# v6_io_12_13_14_15.net
KiCad netlist of a schematic drawn in Altium Designer
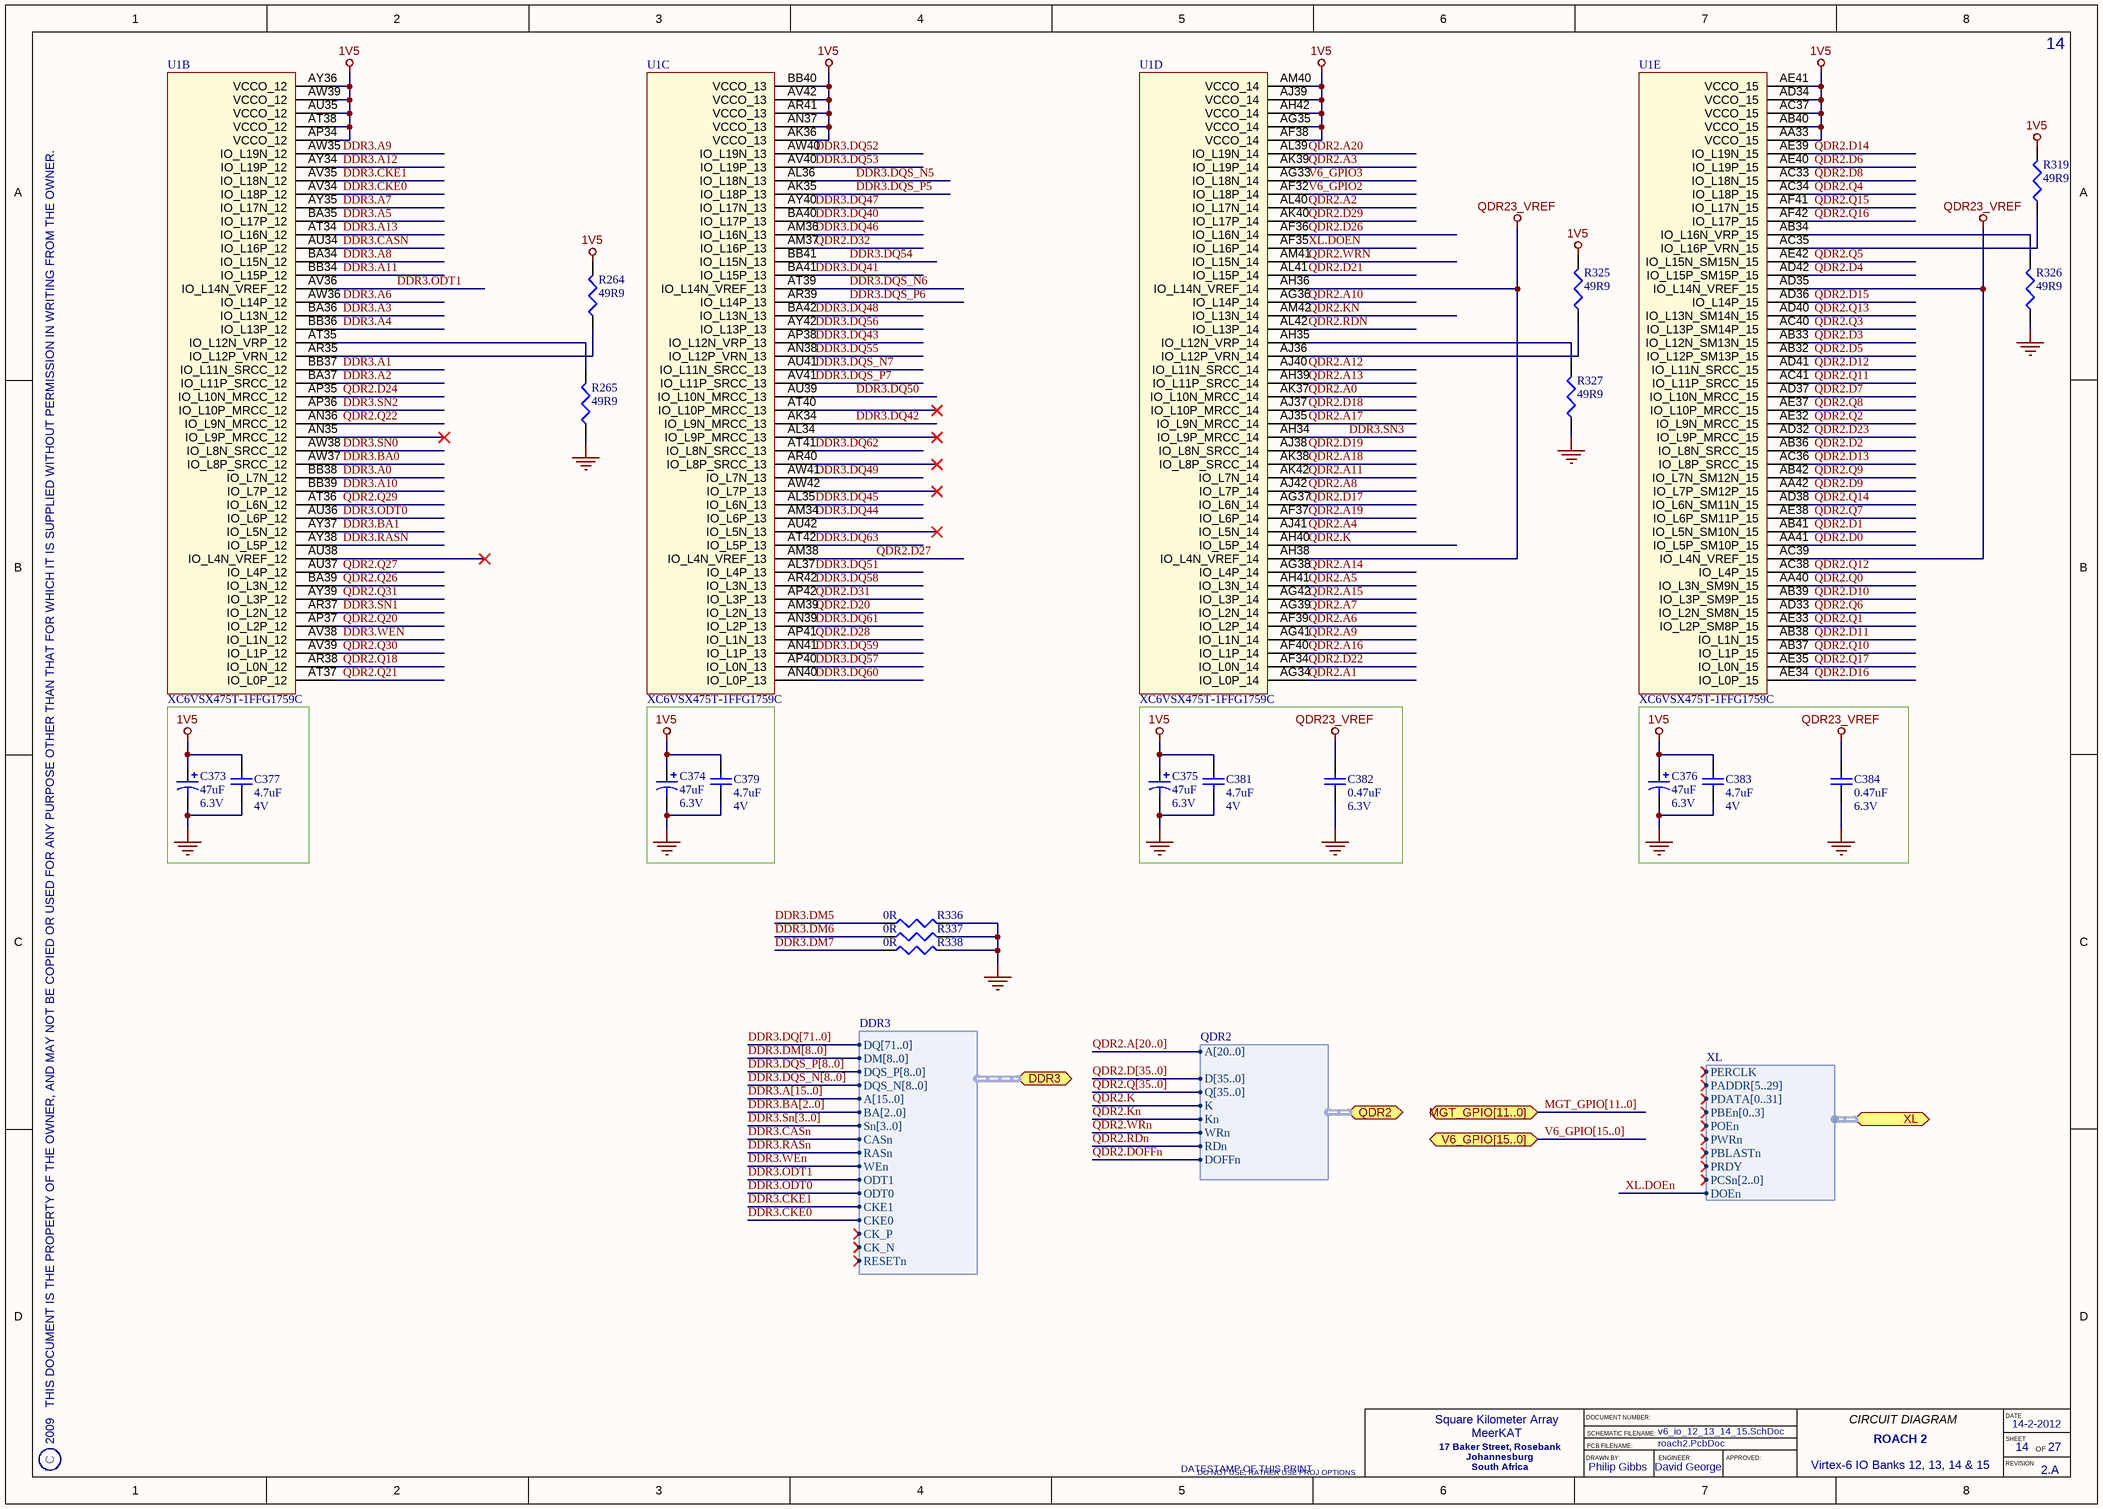
[diagram p0: v6_io_12_13_14_15.SchDoc]

(export (version "E")
  (design (tool "Eeschema 10.0.6"))
  (components
    (comp (ref "C373")
      (value "47uF")
      (footprint "CAPMP3528X120L")
      (description "47uF, Conductive Polymer Chip Capacitor")
      (fields
        (field (name "RATING") "6.3V")
        (field (name "MANUFACTURER") "KEMET")
        (field (name "PARTNUM") "T520T476M006ATE070")
      )
      (libsource (lib "altium_db") (part "CapPol"))
    )
    (comp (ref "C374")
      (value "47uF")
      (footprint "CAPMP3528X120L")
      (description "47uF, Conductive Polymer Chip Capacitor")
      (fields
        (field (name "RATING") "6.3V")
        (field (name "MANUFACTURER") "KEMET")
        (field (name "PARTNUM") "T520T476M006ATE070")
      )
      (libsource (lib "altium_db") (part "CapPol"))
    )
    (comp (ref "C375")
      (value "47uF")
      (footprint "CAPMP3528X120L")
      (description "47uF, Conductive Polymer Chip Capacitor")
      (fields
        (field (name "RATING") "6.3V")
        (field (name "MANUFACTURER") "KEMET")
        (field (name "PARTNUM") "T520T476M006ATE070")
      )
      (libsource (lib "altium_db") (part "CapPol"))
    )
    (comp (ref "C376")
      (value "47uF")
      (footprint "CAPMP3528X120L")
      (description "47uF, Conductive Polymer Chip Capacitor")
      (fields
        (field (name "RATING") "6.3V")
        (field (name "MANUFACTURER") "KEMET")
        (field (name "PARTNUM") "T520T476M006ATE070")
      )
      (libsource (lib "altium_db") (part "CapPol"))
    )
    (comp (ref "C377")
      (value "4.7uF")
      (footprint "CAPC1005X60L")
      (description "4.7uF, Ceramic Capacitor")
      (fields
        (field (name "RATING") "4V")
        (field (name "MANUFACTURER") "MURATA")
        (field (name "PARTNUM") "AMK105BJ475MV-F")
      )
      (libsource (lib "altium_db") (part "CapStd"))
    )
    (comp (ref "C379")
      (value "4.7uF")
      (footprint "CAPC1005X60L")
      (description "4.7uF, Ceramic Capacitor")
      (fields
        (field (name "RATING") "4V")
        (field (name "MANUFACTURER") "MURATA")
        (field (name "PARTNUM") "AMK105BJ475MV-F")
      )
      (libsource (lib "altium_db") (part "CapStd"))
    )
    (comp (ref "C381")
      (value "4.7uF")
      (footprint "CAPC1005X60L")
      (description "4.7uF, Ceramic Capacitor")
      (fields
        (field (name "RATING") "4V")
        (field (name "MANUFACTURER") "MURATA")
        (field (name "PARTNUM") "AMK105BJ475MV-F")
      )
      (libsource (lib "altium_db") (part "CapStd"))
    )
    (comp (ref "C382")
      (value "0.47uF")
      (footprint "CAPC1005X55L")
      (description "0.47uF, Ceramic Capacitor")
      (fields
        (field (name "RATING") "6.3V")
        (field (name "MANUFACTURER") "MURATA")
        (field (name "PARTNUM") "GRM155R60J474KE19")
      )
      (libsource (lib "altium_db") (part "CapStd"))
    )
    (comp (ref "C383")
      (value "4.7uF")
      (footprint "CAPC1005X60L")
      (description "4.7uF, Ceramic Capacitor")
      (fields
        (field (name "RATING") "4V")
        (field (name "MANUFACTURER") "MURATA")
        (field (name "PARTNUM") "AMK105BJ475MV-F")
      )
      (libsource (lib "altium_db") (part "CapStd"))
    )
    (comp (ref "C384")
      (value "0.47uF")
      (footprint "CAPC1005X55L")
      (description "0.47uF, Ceramic Capacitor")
      (fields
        (field (name "RATING") "6.3V")
        (field (name "MANUFACTURER") "MURATA")
        (field (name "PARTNUM") "GRM155R60J474KE19")
      )
      (libsource (lib "altium_db") (part "CapStd"))
    )
    (comp (ref "R264")
      (value "49R9")
      (footprint "RESC1005X40L")
      (description "49R9, 1.1mm x 0.5mm, Thick Film Resistor")
      (fields (field (name "MANUFACTURER") "ROYALOHM") (field (name "PARTNUM") "0402WGF499JT1E"))
      (libsource (lib "altium_db") (part "ResStd"))
    )
    (comp (ref "R265")
      (value "49R9")
      (footprint "RESC1005X40L")
      (description "49R9, 1.1mm x 0.5mm, Thick Film Resistor")
      (fields (field (name "MANUFACTURER") "ROYALOHM") (field (name "PARTNUM") "0402WGF499JT1E"))
      (libsource (lib "altium_db") (part "ResStd"))
    )
    (comp (ref "R319")
      (value "49R9")
      (footprint "RESC1005X40L")
      (description "49R9, 1.1mm x 0.5mm, Thick Film Resistor")
      (fields (field (name "MANUFACTURER") "ROYALOHM") (field (name "PARTNUM") "0402WGF499JT1E"))
      (libsource (lib "altium_db") (part "ResStd"))
    )
    (comp (ref "R325")
      (value "49R9")
      (footprint "RESC1005X40L")
      (description "49R9, 1.1mm x 0.5mm, Thick Film Resistor")
      (fields (field (name "MANUFACTURER") "ROYALOHM") (field (name "PARTNUM") "0402WGF499JT1E"))
      (libsource (lib "altium_db") (part "ResStd"))
    )
    (comp (ref "R326")
      (value "49R9")
      (footprint "RESC1005X40L")
      (description "49R9, 1.1mm x 0.5mm, Thick Film Resistor")
      (fields (field (name "MANUFACTURER") "ROYALOHM") (field (name "PARTNUM") "0402WGF499JT1E"))
      (libsource (lib "altium_db") (part "ResStd"))
    )
    (comp (ref "R327")
      (value "49R9")
      (footprint "RESC1005X40L")
      (description "49R9, 1.1mm x 0.5mm, Thick Film Resistor")
      (fields (field (name "MANUFACTURER") "ROYALOHM") (field (name "PARTNUM") "0402WGF499JT1E"))
      (libsource (lib "altium_db") (part "ResStd"))
    )
    (comp (ref "R336")
      (value "0R")
      (footprint "RESC1005X40L")
      (description "0R, 1.1mm x 0.5mm, Thick Film Resistor")
      (fields (field (name "MANUFACTURER") "ROYALOHM") (field (name "PARTNUM") "0402WG00000T1E"))
      (libsource (lib "altium_db") (part "ResStd"))
    )
    (comp (ref "R337")
      (value "0R")
      (footprint "RESC1005X40L")
      (description "0R, 1.1mm x 0.5mm, Thick Film Resistor")
      (fields (field (name "MANUFACTURER") "ROYALOHM") (field (name "PARTNUM") "0402WG00000T1E"))
      (libsource (lib "altium_db") (part "ResStd"))
    )
    (comp (ref "R338")
      (value "0R")
      (footprint "RESC1005X40L")
      (description "0R, 1.1mm x 0.5mm, Thick Film Resistor")
      (fields (field (name "MANUFACTURER") "ROYALOHM") (field (name "PARTNUM") "0402WG00000T1E"))
      (libsource (lib "altium_db") (part "ResStd"))
    )
    (comp (ref "U1")
      (value "XC6VSX475T-1FFG1759C")
      (footprint "FFG1759")
      (description "Virtex-6 475SXT 1760-pin FPGA")
      (fields (field (name "MANUFACTURER") "Xilinx"))
      (libsource (lib "altium_db") (part "XC6VSX475T-1FFG1759C"))
    )
  )
  (nets
    (net (code "113") (name "/DDR3.A0") (class "Default")
      (node (ref "U1") (pin "BB38") (pinfunction "IO_L7N_12_BB38") (pintype "passive"))
    )
    (net (code "114") (name "/DDR3.A1") (class "Default")
      (node (ref "U1") (pin "BB37") (pinfunction "IO_L11N_SRCC_12_BB37") (pintype "passive"))
    )
    (net (code "115") (name "/DDR3.A2") (class "Default")
      (node (ref "U1") (pin "BA37") (pinfunction "IO_L11P_SRCC_12_BA37") (pintype "passive"))
    )
    (net (code "116") (name "/DDR3.A3") (class "Default")
      (node (ref "U1") (pin "BA36") (pinfunction "IO_L13N_12_BA36") (pintype "passive"))
    )
    (net (code "117") (name "/DDR3.A4") (class "Default")
      (node (ref "U1") (pin "BB36") (pinfunction "IO_L13P_12_BB36") (pintype "passive"))
    )
    (net (code "118") (name "/DDR3.A5") (class "Default")
      (node (ref "U1") (pin "BA35") (pinfunction "IO_L17P_12_BA35") (pintype "passive"))
    )
    (net (code "119") (name "/DDR3.A6") (class "Default")
      (node (ref "U1") (pin "AW36") (pinfunction "IO_L14P_12_AW36") (pintype "passive"))
    )
    (net (code "120") (name "/DDR3.A7") (class "Default")
      (node (ref "U1") (pin "AY35") (pinfunction "IO_L17N_12_AY35") (pintype "passive"))
    )
    (net (code "121") (name "/DDR3.A8") (class "Default")
      (node (ref "U1") (pin "BA34") (pinfunction "IO_L15N_12_BA34") (pintype "passive"))
    )
    (net (code "122") (name "/DDR3.A9") (class "Default")
      (node (ref "U1") (pin "AW35") (pinfunction "IO_L19N_12_AW35") (pintype "passive"))
    )
    (net (code "123") (name "/DDR3.A10") (class "Default")
      (node (ref "U1") (pin "BB39") (pinfunction "IO_L7P_12_BB39") (pintype "passive"))
    )
    (net (code "124") (name "/DDR3.A11") (class "Default")
      (node (ref "U1") (pin "BB34") (pinfunction "IO_L15P_12_BB34") (pintype "passive"))
    )
    (net (code "125") (name "/DDR3.A12") (class "Default")
      (node (ref "U1") (pin "AY34") (pinfunction "IO_L19P_12_AY34") (pintype "passive"))
    )
    (net (code "126") (name "/DDR3.A13") (class "Default")
      (node (ref "U1") (pin "AT34") (pinfunction "IO_L16N_12_AT34") (pintype "passive"))
    )
    (net (code "128") (name "/DDR3.BA0") (class "Default")
      (node (ref "U1") (pin "AW37") (pinfunction "IO_L8P_SRCC_12_AW37") (pintype "passive"))
    )
    (net (code "129") (name "/DDR3.BA1") (class "Default")
      (node (ref "U1") (pin "AY37") (pinfunction "IO_L5N_12_AY37") (pintype "passive"))
    )
    (net (code "131") (name "/DDR3.CASN") (class "Default")
      (node (ref "U1") (pin "AU34") (pinfunction "IO_L16P_12_AU34") (pintype "passive"))
    )
    (net (code "133") (name "/DDR3.CKE0") (class "Default")
      (node (ref "U1") (pin "AV34") (pinfunction "IO_L18P_12_AV34") (pintype "passive"))
    )
    (net (code "134") (name "/DDR3.CKE1") (class "Default")
      (node (ref "U1") (pin "AV35") (pinfunction "IO_L18N_12_AV35") (pintype "passive"))
    )
    (net (code "135") (name "/DDR3.DM5") (class "Default")
      (node (ref "R336") (pin "1") (pinfunction "1_1") (pintype "passive"))
    )
    (net (code "136") (name "/DDR3.DM6") (class "Default")
      (node (ref "R337") (pin "1") (pinfunction "1_1") (pintype "passive"))
    )
    (net (code "137") (name "/DDR3.DM7") (class "Default")
      (node (ref "R338") (pin "1") (pinfunction "1_1") (pintype "passive"))
    )
    (net (code "139") (name "/DDR3.DQ40") (class "Default")
      (node (ref "U1") (pin "BA40") (pinfunction "IO_L17P_13_BA40") (pintype "passive"))
    )
    (net (code "140") (name "/DDR3.DQ41") (class "Default")
      (node (ref "U1") (pin "BA41") (pinfunction "IO_L15P_13_BA41") (pintype "passive"))
    )
    (net (code "141") (name "/DDR3.DQ42") (class "Default")
      (node (ref "U1") (pin "AK34") (pinfunction "IO_L9N_MRCC_13_AK34") (pintype "passive"))
    )
    (net (code "142") (name "/DDR3.DQ43") (class "Default")
      (node (ref "U1") (pin "AP38") (pinfunction "IO_L12N_VRP_13_AP38") (pintype "passive"))
    )
    (net (code "143") (name "/DDR3.DQ44") (class "Default")
      (node (ref "U1") (pin "AM34") (pinfunction "IO_L6P_13_AM34") (pintype "passive"))
    )
    (net (code "144") (name "/DDR3.DQ45") (class "Default")
      (node (ref "U1") (pin "AL35") (pinfunction "IO_L6N_13_AL35") (pintype "passive"))
    )
    (net (code "145") (name "/DDR3.DQ46") (class "Default")
      (node (ref "U1") (pin "AM36") (pinfunction "IO_L16N_13_AM36") (pintype "passive"))
    )
    (net (code "146") (name "/DDR3.DQ47") (class "Default")
      (node (ref "U1") (pin "AY40") (pinfunction "IO_L17N_13_AY40") (pintype "passive"))
    )
    (net (code "147") (name "/DDR3.DQ48") (class "Default")
      (node (ref "U1") (pin "BA42") (pinfunction "IO_L13N_13_BA42") (pintype "passive"))
    )
    (net (code "148") (name "/DDR3.DQ49") (class "Default")
      (node (ref "U1") (pin "AW41") (pinfunction "IO_L7N_13_AW41") (pintype "passive"))
    )
    (net (code "149") (name "/DDR3.DQ50") (class "Default")
      (node (ref "U1") (pin "AU39") (pinfunction "IO_L10N_MRCC_13_AU39") (pintype "passive"))
    )
    (net (code "150") (name "/DDR3.DQ51") (class "Default")
      (node (ref "U1") (pin "AL37") (pinfunction "IO_L4P_13_AL37") (pintype "passive"))
    )
    (net (code "151") (name "/DDR3.DQ52") (class "Default")
      (node (ref "U1") (pin "AW40") (pinfunction "IO_L19N_13_AW40") (pintype "passive"))
    )
    (net (code "152") (name "/DDR3.DQ53") (class "Default")
      (node (ref "U1") (pin "AV40") (pinfunction "IO_L19P_13_AV40") (pintype "passive"))
    )
    (net (code "153") (name "/DDR3.DQ54") (class "Default")
      (node (ref "U1") (pin "BB41") (pinfunction "IO_L15N_13_BB41") (pintype "passive"))
    )
    (net (code "154") (name "/DDR3.DQ55") (class "Default")
      (node (ref "U1") (pin "AN38") (pinfunction "IO_L12P_VRN_13_AN38") (pintype "passive"))
    )
    (net (code "155") (name "/DDR3.DQ56") (class "Default")
      (node (ref "U1") (pin "AY42") (pinfunction "IO_L13P_13_AY42") (pintype "passive"))
    )
    (net (code "156") (name "/DDR3.DQ57") (class "Default")
      (node (ref "U1") (pin "AP40") (pinfunction "IO_L0N_13_AP40") (pintype "passive"))
    )
    (net (code "157") (name "/DDR3.DQ58") (class "Default")
      (node (ref "U1") (pin "AR42") (pinfunction "IO_L3N_13_AR42") (pintype "passive"))
    )
    (net (code "158") (name "/DDR3.DQ59") (class "Default")
      (node (ref "U1") (pin "AN41") (pinfunction "IO_L1P_13_AN41") (pintype "passive"))
    )
    (net (code "159") (name "/DDR3.DQ60") (class "Default")
      (node (ref "U1") (pin "AN40") (pinfunction "IO_L0P_13_AN40") (pintype "passive"))
    )
    (net (code "160") (name "/DDR3.DQ61") (class "Default")
      (node (ref "U1") (pin "AN39") (pinfunction "IO_L2P_13_AN39") (pintype "passive"))
    )
    (net (code "161") (name "/DDR3.DQ62") (class "Default")
      (node (ref "U1") (pin "AT41") (pinfunction "IO_L8N_SRCC_13_AT41") (pintype "passive"))
    )
    (net (code "162") (name "/DDR3.DQ63") (class "Default")
      (node (ref "U1") (pin "AT42") (pinfunction "IO_L5P_13_AT42") (pintype "passive"))
    )
    (net (code "163") (name "/DDR3.DQS_N5") (class "Default")
      (node (ref "U1") (pin "AL36") (pinfunction "IO_L18N_13_AL36") (pintype "passive"))
    )
    (net (code "164") (name "/DDR3.DQS_N6") (class "Default")
      (node (ref "U1") (pin "AT39") (pinfunction "IO_L14N_VREF_13_AT39") (pintype "passive"))
    )
    (net (code "165") (name "/DDR3.DQS_N7") (class "Default")
      (node (ref "U1") (pin "AU41") (pinfunction "IO_L11N_SRCC_13_AU41") (pintype "passive"))
    )
    (net (code "167") (name "/DDR3.DQS_P5") (class "Default")
      (node (ref "U1") (pin "AK35") (pinfunction "IO_L18P_13_AK35") (pintype "passive"))
    )
    (net (code "168") (name "/DDR3.DQS_P6") (class "Default")
      (node (ref "U1") (pin "AR39") (pinfunction "IO_L14P_13_AR39") (pintype "passive"))
    )
    (net (code "169") (name "/DDR3.DQS_P7") (class "Default")
      (node (ref "U1") (pin "AV41") (pinfunction "IO_L11P_SRCC_13_AV41") (pintype "passive"))
    )
    (net (code "172") (name "/DDR3.ODT0") (class "Default")
      (node (ref "U1") (pin "AU36") (pinfunction "IO_L6P_12_AU36") (pintype "passive"))
    )
    (net (code "173") (name "/DDR3.ODT1") (class "Default")
      (node (ref "U1") (pin "AV36") (pinfunction "IO_L14N_VREF_12_AV36") (pintype "passive"))
    )
    (net (code "174") (name "/DDR3.RASN") (class "Default")
      (node (ref "U1") (pin "AY38") (pinfunction "IO_L5P_12_AY38") (pintype "passive"))
    )
    (net (code "176") (name "/DDR3.SN0") (class "Default")
      (node (ref "U1") (pin "AW38") (pinfunction "IO_L8N_SRCC_12_AW38") (pintype "passive"))
    )
    (net (code "177") (name "/DDR3.SN1") (class "Default")
      (node (ref "U1") (pin "AR37") (pinfunction "IO_L2N_12_AR37") (pintype "passive"))
    )
    (net (code "178") (name "/DDR3.SN2") (class "Default")
      (node (ref "U1") (pin "AP36") (pinfunction "IO_L10P_MRCC_12_AP36") (pintype "passive"))
    )
    (net (code "179") (name "/DDR3.SN3") (class "Default")
      (node (ref "U1") (pin "AH34") (pinfunction "IO_L9P_MRCC_14_AH34") (pintype "passive"))
    )
    (net (code "180") (name "/DDR3.WEN") (class "Default")
      (node (ref "U1") (pin "AV38") (pinfunction "IO_L1N_12_AV38") (pintype "passive"))
    )
    (net (code "184") (name "/QDR2.A0") (class "Default")
      (node (ref "U1") (pin "AK37") (pinfunction "IO_L10N_MRCC_14_AK37") (pintype "passive"))
    )
    (net (code "185") (name "/QDR2.A1") (class "Default")
      (node (ref "U1") (pin "AG34") (pinfunction "IO_L0P_14_AG34") (pintype "passive"))
    )
    (net (code "186") (name "/QDR2.A2") (class "Default")
      (node (ref "U1") (pin "AL40") (pinfunction "IO_L17N_14_AL40") (pintype "passive"))
    )
    (net (code "187") (name "/QDR2.A3") (class "Default")
      (node (ref "U1") (pin "AK39") (pinfunction "IO_L19P_14_AK39") (pintype "passive"))
    )
    (net (code "188") (name "/QDR2.A4") (class "Default")
      (node (ref "U1") (pin "AJ41") (pinfunction "IO_L5N_14_AJ41") (pintype "passive"))
    )
    (net (code "189") (name "/QDR2.A5") (class "Default")
      (node (ref "U1") (pin "AH41") (pinfunction "IO_L3N_14_AH41") (pintype "passive"))
    )
    (net (code "190") (name "/QDR2.A6") (class "Default")
      (node (ref "U1") (pin "AF39") (pinfunction "IO_L2P_14_AF39") (pintype "passive"))
    )
    (net (code "191") (name "/QDR2.A7") (class "Default")
      (node (ref "U1") (pin "AG39") (pinfunction "IO_L2N_14_AG39") (pintype "passive"))
    )
    (net (code "192") (name "/QDR2.A8") (class "Default")
      (node (ref "U1") (pin "AJ42") (pinfunction "IO_L7P_14_AJ42") (pintype "passive"))
    )
    (net (code "193") (name "/QDR2.A9") (class "Default")
      (node (ref "U1") (pin "AG41") (pinfunction "IO_L1N_14_AG41") (pintype "passive"))
    )
    (net (code "194") (name "/QDR2.A10") (class "Default")
      (node (ref "U1") (pin "AG36") (pinfunction "IO_L14P_14_AG36") (pintype "passive"))
    )
    (net (code "195") (name "/QDR2.A11") (class "Default")
      (node (ref "U1") (pin "AK42") (pinfunction "IO_L7N_14_AK42") (pintype "passive"))
    )
    (net (code "196") (name "/QDR2.A12") (class "Default")
      (node (ref "U1") (pin "AJ40") (pinfunction "IO_L11N_SRCC_14_AJ40") (pintype "passive"))
    )
    (net (code "197") (name "/QDR2.A13") (class "Default")
      (node (ref "U1") (pin "AH39") (pinfunction "IO_L11P_SRCC_14_AH39") (pintype "passive"))
    )
    (net (code "198") (name "/QDR2.A14") (class "Default")
      (node (ref "U1") (pin "AG38") (pinfunction "IO_L4P_14_AG38") (pintype "passive"))
    )
    (net (code "199") (name "/QDR2.A15") (class "Default")
      (node (ref "U1") (pin "AG42") (pinfunction "IO_L3P_14_AG42") (pintype "passive"))
    )
    (net (code "200") (name "/QDR2.A16") (class "Default")
      (node (ref "U1") (pin "AF40") (pinfunction "IO_L1P_14_AF40") (pintype "passive"))
    )
    (net (code "201") (name "/QDR2.A17") (class "Default")
      (node (ref "U1") (pin "AJ35") (pinfunction "IO_L9N_MRCC_14_AJ35") (pintype "passive"))
    )
    (net (code "202") (name "/QDR2.A18") (class "Default")
      (node (ref "U1") (pin "AK38") (pinfunction "IO_L8P_SRCC_14_AK38") (pintype "passive"))
    )
    (net (code "203") (name "/QDR2.A19") (class "Default")
      (node (ref "U1") (pin "AF37") (pinfunction "IO_L6P_14_AF37") (pintype "passive"))
    )
    (net (code "204") (name "/QDR2.A20") (class "Default")
      (node (ref "U1") (pin "AL39") (pinfunction "IO_L19N_14_AL39") (pintype "passive"))
    )
    (net (code "205") (name "/QDR2.D0") (class "Default")
      (node (ref "U1") (pin "AA41") (pinfunction "IO_L5P_SM10P_15_AA41") (pintype "passive"))
    )
    (net (code "206") (name "/QDR2.D1") (class "Default")
      (node (ref "U1") (pin "AB41") (pinfunction "IO_L5N_SM10N_15_AB41") (pintype "passive"))
    )
    (net (code "207") (name "/QDR2.D2") (class "Default")
      (node (ref "U1") (pin "AB36") (pinfunction "IO_L8N_SRCC_15_AB36") (pintype "passive"))
    )
    (net (code "208") (name "/QDR2.D3") (class "Default")
      (node (ref "U1") (pin "AB33") (pinfunction "IO_L12N_SM13N_15_AB33") (pintype "passive"))
    )
    (net (code "209") (name "/QDR2.D4") (class "Default")
      (node (ref "U1") (pin "AD42") (pinfunction "IO_L15P_SM15P_15_AD42") (pintype "passive"))
    )
    (net (code "210") (name "/QDR2.D5") (class "Default")
      (node (ref "U1") (pin "AB32") (pinfunction "IO_L12P_SM13P_15_AB32") (pintype "passive"))
    )
    (net (code "211") (name "/QDR2.D6") (class "Default")
      (node (ref "U1") (pin "AE40") (pinfunction "IO_L19P_15_AE40") (pintype "passive"))
    )
    (net (code "212") (name "/QDR2.D7") (class "Default")
      (node (ref "U1") (pin "AD37") (pinfunction "IO_L10N_MRCC_15_AD37") (pintype "passive"))
    )
    (net (code "213") (name "/QDR2.D8") (class "Default")
      (node (ref "U1") (pin "AC33") (pinfunction "IO_L18N_15_AC33") (pintype "passive"))
    )
    (net (code "214") (name "/QDR2.D9") (class "Default")
      (node (ref "U1") (pin "AA42") (pinfunction "IO_L7P_SM12P_15_AA42") (pintype "passive"))
    )
    (net (code "215") (name "/QDR2.D10") (class "Default")
      (node (ref "U1") (pin "AB39") (pinfunction "IO_L3P_SM9P_15_AB39") (pintype "passive"))
    )
    (net (code "216") (name "/QDR2.D11") (class "Default")
      (node (ref "U1") (pin "AB38") (pinfunction "IO_L1N_15_AB38") (pintype "passive"))
    )
    (net (code "217") (name "/QDR2.D12") (class "Default")
      (node (ref "U1") (pin "AD41") (pinfunction "IO_L11N_SRCC_15_AD41") (pintype "passive"))
    )
    (net (code "218") (name "/QDR2.D13") (class "Default")
      (node (ref "U1") (pin "AC36") (pinfunction "IO_L8P_SRCC_15_AC36") (pintype "passive"))
    )
    (net (code "219") (name "/QDR2.D14") (class "Default")
      (node (ref "U1") (pin "AE39") (pinfunction "IO_L19N_15_AE39") (pintype "passive"))
    )
    (net (code "220") (name "/QDR2.D15") (class "Default")
      (node (ref "U1") (pin "AD36") (pinfunction "IO_L14P_15_AD36") (pintype "passive"))
    )
    (net (code "221") (name "/QDR2.D16") (class "Default")
      (node (ref "U1") (pin "AE34") (pinfunction "IO_L0P_15_AE34") (pintype "passive"))
    )
    (net (code "222") (name "/QDR2.D17") (class "Default")
      (node (ref "U1") (pin "AG37") (pinfunction "IO_L6N_14_AG37") (pintype "passive"))
    )
    (net (code "223") (name "/QDR2.D18") (class "Default")
      (node (ref "U1") (pin "AJ37") (pinfunction "IO_L10P_MRCC_14_AJ37") (pintype "passive"))
    )
    (net (code "224") (name "/QDR2.D19") (class "Default")
      (node (ref "U1") (pin "AJ38") (pinfunction "IO_L8N_SRCC_14_AJ38") (pintype "passive"))
    )
    (net (code "225") (name "/QDR2.D20") (class "Default")
      (node (ref "U1") (pin "AM39") (pinfunction "IO_L2N_13_AM39") (pintype "passive"))
    )
    (net (code "226") (name "/QDR2.D21") (class "Default")
      (node (ref "U1") (pin "AL41") (pinfunction "IO_L15P_14_AL41") (pintype "passive"))
    )
    (net (code "227") (name "/QDR2.D22") (class "Default")
      (node (ref "U1") (pin "AF34") (pinfunction "IO_L0N_14_AF34") (pintype "passive"))
    )
    (net (code "228") (name "/QDR2.D23") (class "Default")
      (node (ref "U1") (pin "AD32") (pinfunction "IO_L9P_MRCC_15_AD32") (pintype "passive"))
    )
    (net (code "229") (name "/QDR2.D24") (class "Default")
      (node (ref "U1") (pin "AP35") (pinfunction "IO_L10N_MRCC_12_AP35") (pintype "passive"))
    )
    (net (code "230") (name "/QDR2.D26") (class "Default")
      (node (ref "U1") (pin "AF36") (pinfunction "IO_L16N_14_AF36") (pintype "passive"))
    )
    (net (code "231") (name "/QDR2.D27") (class "Default")
      (node (ref "U1") (pin "AM38") (pinfunction "IO_L4N_VREF_13_AM38") (pintype "passive"))
    )
    (net (code "232") (name "/QDR2.D28") (class "Default")
      (node (ref "U1") (pin "AP41") (pinfunction "IO_L1N_13_AP41") (pintype "passive"))
    )
    (net (code "233") (name "/QDR2.D29") (class "Default")
      (node (ref "U1") (pin "AK40") (pinfunction "IO_L17P_14_AK40") (pintype "passive"))
    )
    (net (code "234") (name "/QDR2.D31") (class "Default")
      (node (ref "U1") (pin "AP42") (pinfunction "IO_L3P_13_AP42") (pintype "passive"))
    )
    (net (code "235") (name "/QDR2.D32") (class "Default")
      (node (ref "U1") (pin "AM37") (pinfunction "IO_L16P_13_AM37") (pintype "passive"))
    )
    (net (code "238") (name "/QDR2.K") (class "Default")
      (node (ref "U1") (pin "AH40") (pinfunction "IO_L5P_14_AH40") (pintype "passive"))
    )
    (net (code "239") (name "/QDR2.KN") (class "Default")
      (node (ref "U1") (pin "AM42") (pinfunction "IO_L13N_14_AM42") (pintype "passive"))
    )
    (net (code "241") (name "/QDR2.Q0") (class "Default")
      (node (ref "U1") (pin "AA40") (pinfunction "IO_L3N_SM9N_15_AA40") (pintype "passive"))
    )
    (net (code "242") (name "/QDR2.Q1") (class "Default")
      (node (ref "U1") (pin "AE33") (pinfunction "IO_L2P_SM8P_15_AE33") (pintype "passive"))
    )
    (net (code "243") (name "/QDR2.Q2") (class "Default")
      (node (ref "U1") (pin "AE32") (pinfunction "IO_L9N_MRCC_15_AE32") (pintype "passive"))
    )
    (net (code "244") (name "/QDR2.Q3") (class "Default")
      (node (ref "U1") (pin "AC40") (pinfunction "IO_L13P_SM14P_15_AC40") (pintype "passive"))
    )
    (net (code "245") (name "/QDR2.Q4") (class "Default")
      (node (ref "U1") (pin "AC34") (pinfunction "IO_L18P_15_AC34") (pintype "passive"))
    )
    (net (code "246") (name "/QDR2.Q5") (class "Default")
      (node (ref "U1") (pin "AE42") (pinfunction "IO_L15N_SM15N_15_AE42") (pintype "passive"))
    )
    (net (code "247") (name "/QDR2.Q6") (class "Default")
      (node (ref "U1") (pin "AD33") (pinfunction "IO_L2N_SM8N_15_AD33") (pintype "passive"))
    )
    (net (code "248") (name "/QDR2.Q7") (class "Default")
      (node (ref "U1") (pin "AE38") (pinfunction "IO_L6P_SM11P_15_AE38") (pintype "passive"))
    )
    (net (code "249") (name "/QDR2.Q8") (class "Default")
      (node (ref "U1") (pin "AE37") (pinfunction "IO_L10P_MRCC_15_AE37") (pintype "passive"))
    )
    (net (code "250") (name "/QDR2.Q9") (class "Default")
      (node (ref "U1") (pin "AB42") (pinfunction "IO_L7N_SM12N_15_AB42") (pintype "passive"))
    )
    (net (code "251") (name "/QDR2.Q10") (class "Default")
      (node (ref "U1") (pin "AB37") (pinfunction "IO_L1P_15_AB37") (pintype "passive"))
    )
    (net (code "252") (name "/QDR2.Q11") (class "Default")
      (node (ref "U1") (pin "AC41") (pinfunction "IO_L11P_SRCC_15_AC41") (pintype "passive"))
    )
    (net (code "253") (name "/QDR2.Q12") (class "Default")
      (node (ref "U1") (pin "AC38") (pinfunction "IO_L4P_15_AC38") (pintype "passive"))
    )
    (net (code "254") (name "/QDR2.Q13") (class "Default")
      (node (ref "U1") (pin "AD40") (pinfunction "IO_L13N_SM14N_15_AD40") (pintype "passive"))
    )
    (net (code "255") (name "/QDR2.Q14") (class "Default")
      (node (ref "U1") (pin "AD38") (pinfunction "IO_L6N_SM11N_15_AD38") (pintype "passive"))
    )
    (net (code "256") (name "/QDR2.Q15") (class "Default")
      (node (ref "U1") (pin "AF41") (pinfunction "IO_L17N_15_AF41") (pintype "passive"))
    )
    (net (code "257") (name "/QDR2.Q16") (class "Default")
      (node (ref "U1") (pin "AF42") (pinfunction "IO_L17P_15_AF42") (pintype "passive"))
    )
    (net (code "258") (name "/QDR2.Q17") (class "Default")
      (node (ref "U1") (pin "AE35") (pinfunction "IO_L0N_15_AE35") (pintype "passive"))
    )
    (net (code "259") (name "/QDR2.Q18") (class "Default")
      (node (ref "U1") (pin "AR38") (pinfunction "IO_L0N_12_AR38") (pintype "passive"))
    )
    (net (code "260") (name "/QDR2.Q20") (class "Default")
      (node (ref "U1") (pin "AP37") (pinfunction "IO_L2P_12_AP37") (pintype "passive"))
    )
    (net (code "261") (name "/QDR2.Q21") (class "Default")
      (node (ref "U1") (pin "AT37") (pinfunction "IO_L0P_12_AT37") (pintype "passive"))
    )
    (net (code "262") (name "/QDR2.Q22") (class "Default")
      (node (ref "U1") (pin "AN36") (pinfunction "IO_L9N_MRCC_12_AN36") (pintype "passive"))
    )
    (net (code "263") (name "/QDR2.Q26") (class "Default")
      (node (ref "U1") (pin "BA39") (pinfunction "IO_L3N_12_BA39") (pintype "passive"))
    )
    (net (code "264") (name "/QDR2.Q27") (class "Default")
      (node (ref "U1") (pin "AU37") (pinfunction "IO_L4P_12_AU37") (pintype "passive"))
    )
    (net (code "265") (name "/QDR2.Q29") (class "Default")
      (node (ref "U1") (pin "AT36") (pinfunction "IO_L6N_12_AT36") (pintype "passive"))
    )
    (net (code "266") (name "/QDR2.Q30") (class "Default")
      (node (ref "U1") (pin "AV39") (pinfunction "IO_L1P_12_AV39") (pintype "passive"))
    )
    (net (code "267") (name "/QDR2.Q31") (class "Default")
      (node (ref "U1") (pin "AY39") (pinfunction "IO_L3P_12_AY39") (pintype "passive"))
    )
    (net (code "269") (name "/QDR2.RDN") (class "Default")
      (node (ref "U1") (pin "AL42") (pinfunction "IO_L13P_14_AL42") (pintype "passive"))
    )
    (net (code "271") (name "/QDR2.WRN") (class "Default")
      (node (ref "U1") (pin "AM41") (pinfunction "IO_L15N_14_AM41") (pintype "passive"))
    )
    (net (code "274") (name "/V6_GPIO2") (class "Default")
      (node (ref "U1") (pin "AF32") (pinfunction "IO_L18P_14_AF32") (pintype "passive"))
    )
    (net (code "275") (name "/V6_GPIO3") (class "Default")
      (node (ref "U1") (pin "AG33") (pinfunction "IO_L18N_14_AG33") (pintype "passive"))
    )
    (net (code "277") (name "/XL.DOEN") (class "Default")
      (node (ref "U1") (pin "AF35") (pinfunction "IO_L16P_14_AF35") (pintype "passive"))
    )
    (net (code "282") (name "1V5") (class "Default")
      (node (ref "C373") (pin "1") (pinfunction "1_1") (pintype "passive"))
      (node (ref "C374") (pin "1") (pinfunction "1_1") (pintype "passive"))
      (node (ref "C375") (pin "1") (pinfunction "1_1") (pintype "passive"))
      (node (ref "C376") (pin "1") (pinfunction "1_1") (pintype "passive"))
      (node (ref "C377") (pin "2") (pinfunction "2_2") (pintype "passive"))
      (node (ref "C379") (pin "2") (pinfunction "2_2") (pintype "passive"))
      (node (ref "C381") (pin "2") (pinfunction "2_2") (pintype "passive"))
      (node (ref "C383") (pin "2") (pinfunction "2_2") (pintype "passive"))
      (node (ref "R264") (pin "2") (pinfunction "2_2") (pintype "passive"))
      (node (ref "R319") (pin "2") (pinfunction "2_2") (pintype "passive"))
      (node (ref "R325") (pin "2") (pinfunction "2_2") (pintype "passive"))
      (node (ref "U1") (pin "AA33") (pinfunction "VCCO_15_AA33") (pintype "passive"))
      (node (ref "U1") (pin "AB40") (pinfunction "VCCO_15_AB40") (pintype "passive"))
      (node (ref "U1") (pin "AC37") (pinfunction "VCCO_15_AC37") (pintype "passive"))
      (node (ref "U1") (pin "AD34") (pinfunction "VCCO_15_AD34") (pintype "passive"))
      (node (ref "U1") (pin "AE41") (pinfunction "VCCO_15_AE41") (pintype "passive"))
      (node (ref "U1") (pin "AF38") (pinfunction "VCCO_14_AF38") (pintype "passive"))
      (node (ref "U1") (pin "AG35") (pinfunction "VCCO_14_AG35") (pintype "passive"))
      (node (ref "U1") (pin "AH42") (pinfunction "VCCO_14_AH42") (pintype "passive"))
      (node (ref "U1") (pin "AJ39") (pinfunction "VCCO_14_AJ39") (pintype "passive"))
      (node (ref "U1") (pin "AK36") (pinfunction "VCCO_13_AK36") (pintype "passive"))
      (node (ref "U1") (pin "AM40") (pinfunction "VCCO_14_AM40") (pintype "passive"))
      (node (ref "U1") (pin "AN37") (pinfunction "VCCO_13_AN37") (pintype "passive"))
      (node (ref "U1") (pin "AP34") (pinfunction "VCCO_12_AP34") (pintype "passive"))
      (node (ref "U1") (pin "AR41") (pinfunction "VCCO_13_AR41") (pintype "passive"))
      (node (ref "U1") (pin "AT38") (pinfunction "VCCO_12_AT38") (pintype "passive"))
      (node (ref "U1") (pin "AU35") (pinfunction "VCCO_12_AU35") (pintype "passive"))
      (node (ref "U1") (pin "AV42") (pinfunction "VCCO_13_AV42") (pintype "passive"))
      (node (ref "U1") (pin "AW39") (pinfunction "VCCO_12_AW39") (pintype "passive"))
      (node (ref "U1") (pin "AY36") (pinfunction "VCCO_12_AY36") (pintype "passive"))
      (node (ref "U1") (pin "BB40") (pinfunction "VCCO_13_BB40") (pintype "passive"))
    )
    (net (code "283") (name "GND") (class "Default")
      (node (ref "C373") (pin "2") (pinfunction "2_2") (pintype "passive"))
      (node (ref "C374") (pin "2") (pinfunction "2_2") (pintype "passive"))
      (node (ref "C375") (pin "2") (pinfunction "2_2") (pintype "passive"))
      (node (ref "C376") (pin "2") (pinfunction "2_2") (pintype "passive"))
      (node (ref "C377") (pin "1") (pinfunction "1_1") (pintype "passive"))
      (node (ref "C379") (pin "1") (pinfunction "1_1") (pintype "passive"))
      (node (ref "C381") (pin "1") (pinfunction "1_1") (pintype "passive"))
      (node (ref "C382") (pin "1") (pinfunction "1_1") (pintype "passive"))
      (node (ref "C383") (pin "1") (pinfunction "1_1") (pintype "passive"))
      (node (ref "C384") (pin "1") (pinfunction "1_1") (pintype "passive"))
      (node (ref "R265") (pin "1") (pinfunction "1_1") (pintype "passive"))
      (node (ref "R326") (pin "1") (pinfunction "1_1") (pintype "passive"))
      (node (ref "R327") (pin "1") (pinfunction "1_1") (pintype "passive"))
      (node (ref "R336") (pin "2") (pinfunction "2_2") (pintype "passive"))
      (node (ref "R337") (pin "2") (pinfunction "2_2") (pintype "passive"))
      (node (ref "R338") (pin "2") (pinfunction "2_2") (pintype "passive"))
    )
    (net (code "284") (name "Net-(U1B-IO_L12N_VRP_12)") (class "Default")
      (node (ref "R265") (pin "2") (pinfunction "2_2") (pintype "passive"))
      (node (ref "U1") (pin "AT35") (pinfunction "IO_L12N_VRP_12_AT35") (pintype "passive"))
    )
    (net (code "285") (name "Net-(U1B-IO_L12P_VRN_12)") (class "Default")
      (node (ref "R264") (pin "1") (pinfunction "1_1") (pintype "passive"))
      (node (ref "U1") (pin "AR35") (pinfunction "IO_L12P_VRN_12_AR35") (pintype "passive"))
    )
    (net (code "286") (name "Net-(U1D-IO_L12N_VRP_14)") (class "Default")
      (node (ref "R327") (pin "2") (pinfunction "2_2") (pintype "passive"))
      (node (ref "U1") (pin "AH35") (pinfunction "IO_L12N_VRP_14_AH35") (pintype "passive"))
    )
    (net (code "287") (name "Net-(U1D-IO_L12P_VRN_14)") (class "Default")
      (node (ref "R325") (pin "1") (pinfunction "1_1") (pintype "passive"))
      (node (ref "U1") (pin "AJ36") (pinfunction "IO_L12P_VRN_14_AJ36") (pintype "passive"))
    )
    (net (code "288") (name "Net-(U1E-IO_L16N_VRP_15)") (class "Default")
      (node (ref "R326") (pin "2") (pinfunction "2_2") (pintype "passive"))
      (node (ref "U1") (pin "AB34") (pinfunction "IO_L16N_VRP_15_AB34") (pintype "passive"))
    )
    (net (code "289") (name "Net-(U1E-IO_L16P_VRN_15)") (class "Default")
      (node (ref "R319") (pin "1") (pinfunction "1_1") (pintype "passive"))
      (node (ref "U1") (pin "AC35") (pinfunction "IO_L16P_VRN_15_AC35") (pintype "passive"))
    )
    (net (code "290") (name "QDR23_VREF") (class "Default")
      (node (ref "C382") (pin "2") (pinfunction "2_2") (pintype "passive"))
      (node (ref "C384") (pin "2") (pinfunction "2_2") (pintype "passive"))
      (node (ref "U1") (pin "AC39") (pinfunction "IO_L4N_VREF_15_AC39") (pintype "passive"))
      (node (ref "U1") (pin "AD35") (pinfunction "IO_L14N_VREF_15_AD35") (pintype "passive"))
      (node (ref "U1") (pin "AH36") (pinfunction "IO_L14N_VREF_14_AH36") (pintype "passive"))
      (node (ref "U1") (pin "AH38") (pinfunction "IO_L4N_VREF_14_AH38") (pintype "passive"))
    )
    (net (code "291") (name "unconnected-(U1B-IO_L4N_VREF_12-PadAU38)") (class "Default")
      (node (ref "U1") (pin "AU38") (pinfunction "IO_L4N_VREF_12_AU38") (pintype "passive+no_connect"))
    )
    (net (code "292") (name "unconnected-(U1B-IO_L9P_MRCC_12-PadAN35)") (class "Default")
      (node (ref "U1") (pin "AN35") (pinfunction "IO_L9P_MRCC_12_AN35") (pintype "passive+no_connect"))
    )
    (net (code "293") (name "unconnected-(U1C-IO_L5N_13-PadAU42)") (class "Default")
      (node (ref "U1") (pin "AU42") (pinfunction "IO_L5N_13_AU42") (pintype "passive+no_connect"))
    )
    (net (code "294") (name "unconnected-(U1C-IO_L7P_13-PadAW42)") (class "Default")
      (node (ref "U1") (pin "AW42") (pinfunction "IO_L7P_13_AW42") (pintype "passive+no_connect"))
    )
    (net (code "295") (name "unconnected-(U1C-IO_L8P_SRCC_13-PadAR40)") (class "Default")
      (node (ref "U1") (pin "AR40") (pinfunction "IO_L8P_SRCC_13_AR40") (pintype "passive+no_connect"))
    )
    (net (code "296") (name "unconnected-(U1C-IO_L9P_MRCC_13-PadAL34)") (class "Default")
      (node (ref "U1") (pin "AL34") (pinfunction "IO_L9P_MRCC_13_AL34") (pintype "passive+no_connect"))
    )
    (net (code "297") (name "unconnected-(U1C-IO_L10P_MRCC_13-PadAT40)") (class "Default")
      (node (ref "U1") (pin "AT40") (pinfunction "IO_L10P_MRCC_13_AT40") (pintype "passive+no_connect"))
    )
  )
)
